# 3DAG.net
KiCad netlist of a schematic drawn in EAGLE
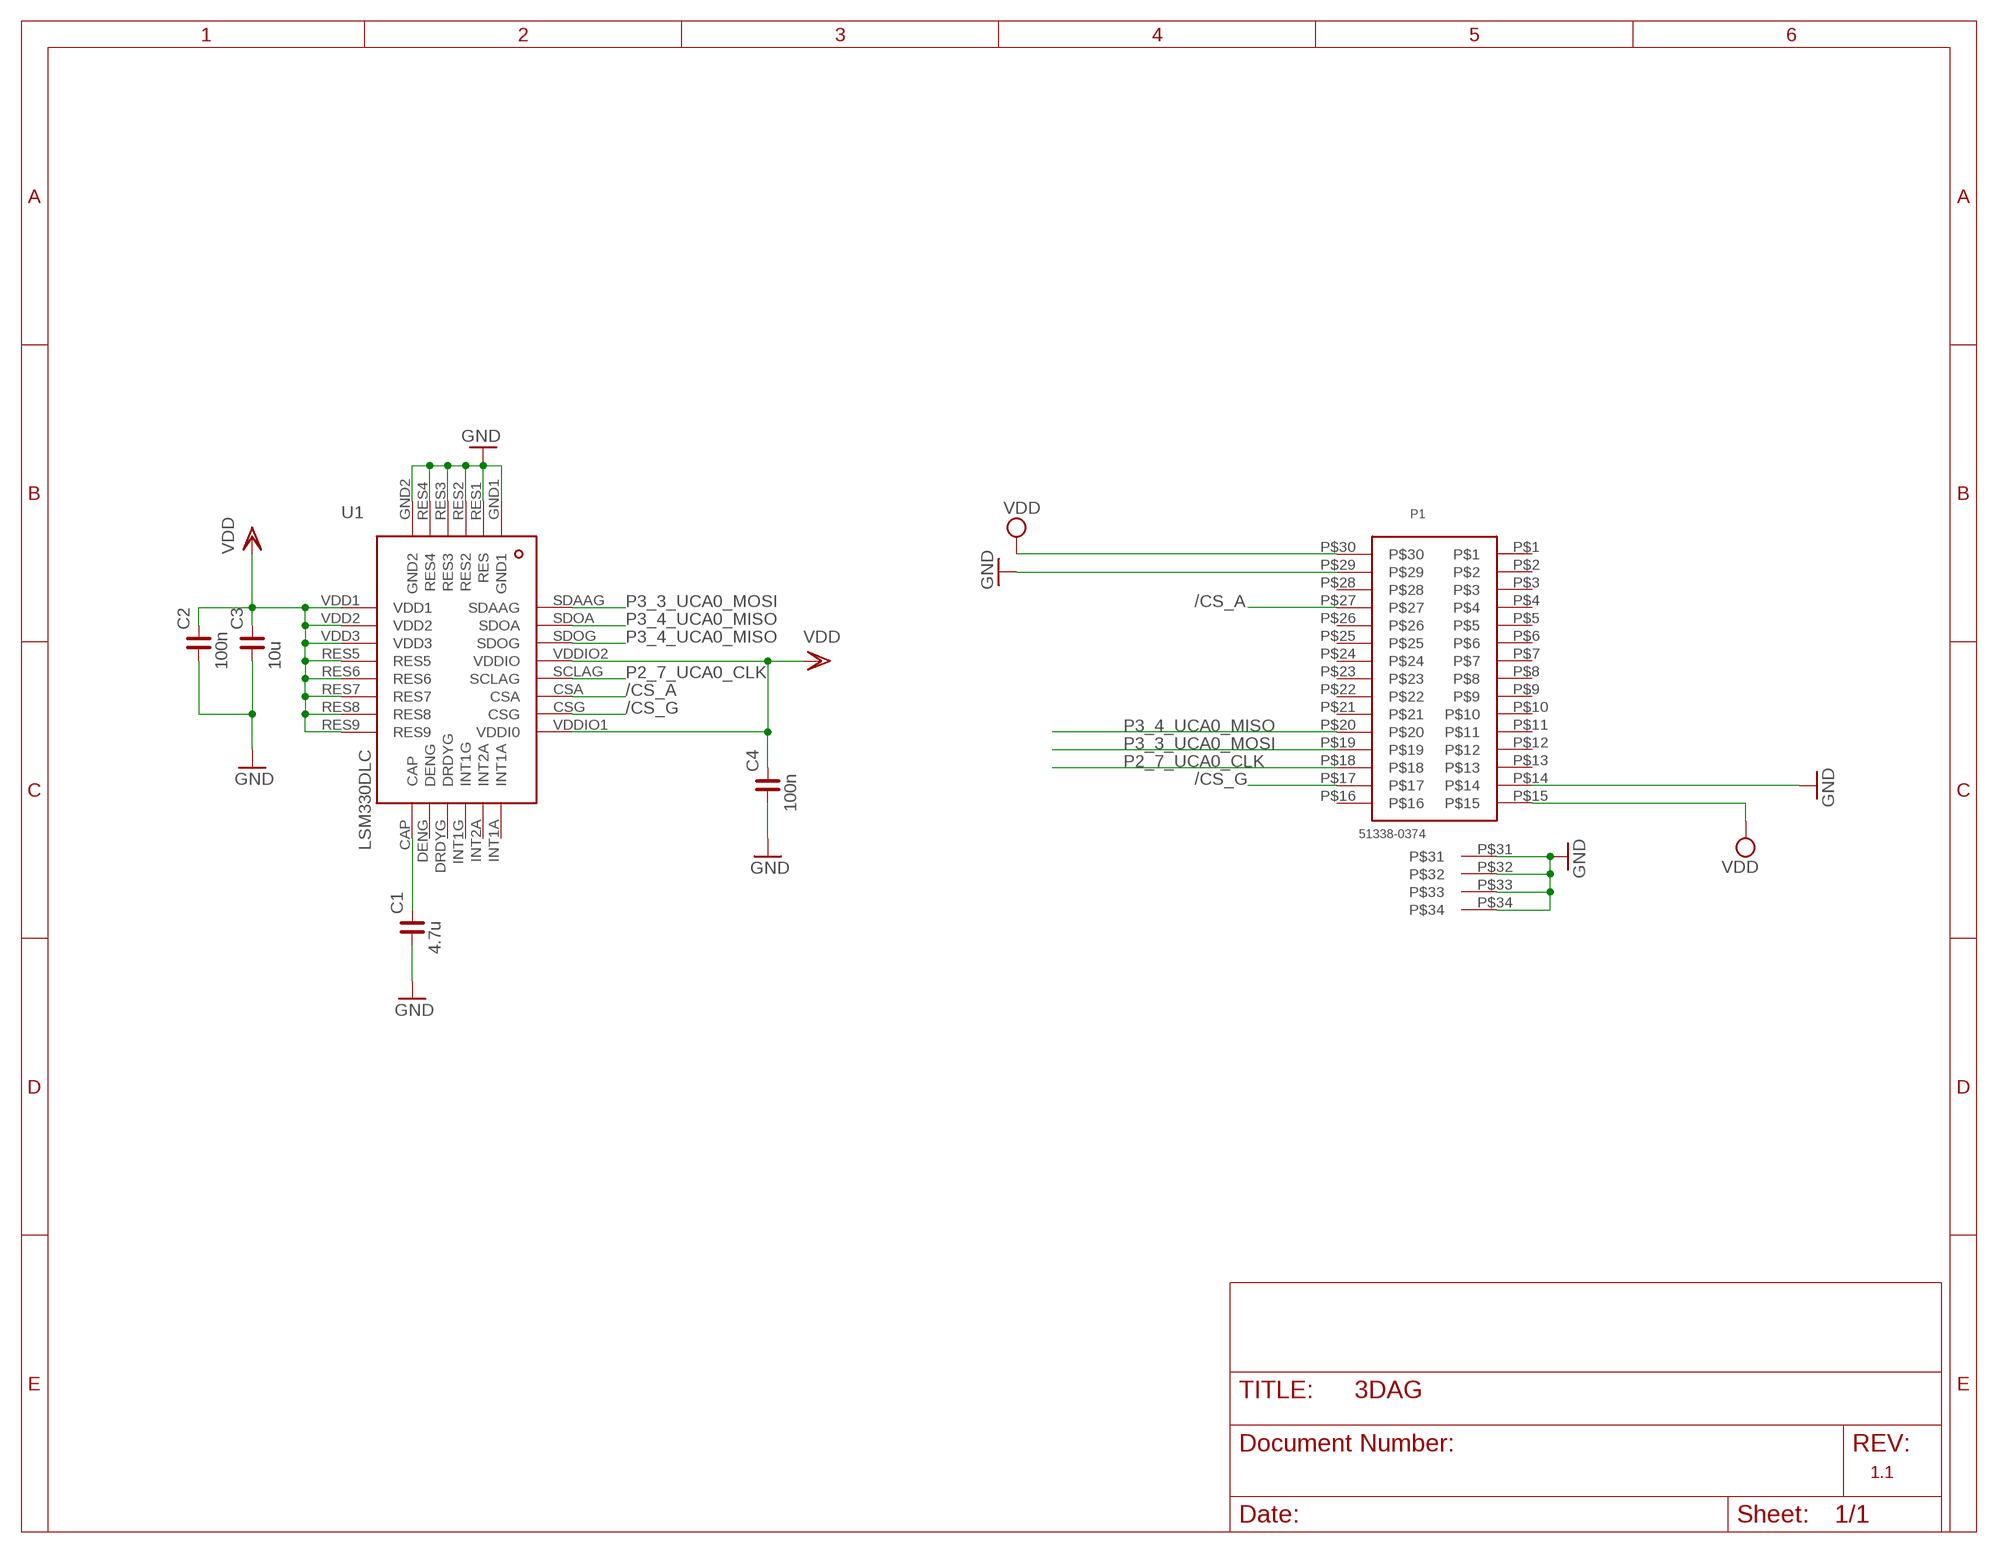
[diagram p0: schematic, sheet 1]

(export (version "E")
  (design (tool "Eeschema 10.0.6"))
  (components
    (comp (ref "C1")
      (value "4.7u")
      (footprint "eagle-import:C0402")
      (libsource (lib "eagle-import") (part "C_0402"))
    )
    (comp (ref "C2")
      (value "100n")
      (footprint "eagle-import:C0402")
      (libsource (lib "eagle-import") (part "C_0402"))
    )
    (comp (ref "C3")
      (value "10u")
      (footprint "eagle-import:C0402")
      (libsource (lib "eagle-import") (part "C_0402"))
    )
    (comp (ref "C4")
      (value "100n")
      (footprint "eagle-import:C0402")
      (libsource (lib "eagle-import") (part "C_0402"))
    )
    (comp (ref "P1")
      (value "51338-0374")
      (footprint "eagle-import:51338-0374_RECEPTACLE")
      (libsource (lib "eagle-import") (part "51338-0374_RECEPTACLE"))
    )
    (comp (ref "U$4")
      (value "LSM330DLC")
      (footprint "eagle-import:LSM330DLC")
      (libsource (lib "eagle-import") (part "LSM330DLC"))
    )
  )
  (nets
    (net (code "1") (name "/P2_7_UCA0_CLK") (class "Default")
      (node (ref "P1") (pin "P$18") (pinfunction "P$18_P$18") (pintype "bidirectional"))
      (node (ref "U$4") (pin "SCLAG") (pinfunction "SCLAG_SCLAG") (pintype "input"))
    )
    (net (code "2") (name "/P3_3_UCA0_MOSI") (class "Default")
      (node (ref "P1") (pin "P$19") (pinfunction "P$19_P$19") (pintype "bidirectional"))
      (node (ref "U$4") (pin "SDAAG") (pinfunction "SDAAG_SDAAG") (pintype "bidirectional"))
    )
    (net (code "3") (name "/P3_4_UCA0_MISO") (class "Default")
      (node (ref "P1") (pin "P$20") (pinfunction "P$20_P$20") (pintype "bidirectional"))
      (node (ref "U$4") (pin "SDOA") (pinfunction "SDOA_SDOA") (pintype "bidirectional"))
      (node (ref "U$4") (pin "SDOG") (pinfunction "SDOG_SDOG") (pintype "bidirectional"))
    )
    (net (code "4") (name "/{slash}CS_A") (class "Default")
      (node (ref "P1") (pin "P$27") (pinfunction "P$27_P$27") (pintype "bidirectional"))
      (node (ref "U$4") (pin "CSA") (pinfunction "CSA_CSA") (pintype "input"))
    )
    (net (code "5") (name "/{slash}CS_G") (class "Default")
      (node (ref "P1") (pin "P$17") (pinfunction "P$17_P$17") (pintype "bidirectional"))
      (node (ref "U$4") (pin "CSG") (pinfunction "CSG_CSG") (pintype "input"))
    )
    (net (code "6") (name "GND") (class "Default")
      (node (ref "C1") (pin "1") (pinfunction "1_1") (pintype "passive"))
      (node (ref "C2") (pin "1") (pinfunction "1_1") (pintype "passive"))
      (node (ref "C3") (pin "1") (pinfunction "1_1") (pintype "passive"))
      (node (ref "C4") (pin "1") (pinfunction "1_1") (pintype "passive"))
      (node (ref "P1") (pin "P$14") (pinfunction "P$14_P$14") (pintype "bidirectional"))
      (node (ref "P1") (pin "P$29") (pinfunction "P$29_P$29") (pintype "bidirectional"))
      (node (ref "P1") (pin "P$31") (pinfunction "P$31_P$31") (pintype "bidirectional"))
      (node (ref "P1") (pin "P$32") (pinfunction "P$32_P$32") (pintype "bidirectional"))
      (node (ref "P1") (pin "P$33") (pinfunction "P$33_P$33") (pintype "bidirectional"))
      (node (ref "P1") (pin "P$34") (pinfunction "P$34_P$34") (pintype "bidirectional"))
      (node (ref "U$4") (pin "GND1") (pinfunction "GND1_GND1") (pintype "power_in"))
      (node (ref "U$4") (pin "GND2") (pinfunction "GND2_GND2") (pintype "power_in"))
      (node (ref "U$4") (pin "RES1") (pinfunction "RES_RES1") (pintype "power_in"))
      (node (ref "U$4") (pin "RES2") (pinfunction "RES2_RES2") (pintype "power_in"))
      (node (ref "U$4") (pin "RES3") (pinfunction "RES3_RES3") (pintype "bidirectional"))
      (node (ref "U$4") (pin "RES4") (pinfunction "RES4_RES4") (pintype "bidirectional"))
    )
    (net (code "7") (name "Net-(C1-Pad2)") (class "Default")
      (node (ref "C1") (pin "2") (pinfunction "2_2") (pintype "passive"))
      (node (ref "U$4") (pin "CAP") (pinfunction "CAP_CAP") (pintype "passive"))
    )
    (net (code "8") (name "VDD") (class "Default")
      (node (ref "C2") (pin "2") (pinfunction "2_2") (pintype "passive"))
      (node (ref "C3") (pin "2") (pinfunction "2_2") (pintype "passive"))
      (node (ref "C4") (pin "2") (pinfunction "2_2") (pintype "passive"))
      (node (ref "P1") (pin "P$15") (pinfunction "P$15_P$15") (pintype "bidirectional"))
      (node (ref "P1") (pin "P$30") (pinfunction "P$30_P$30") (pintype "bidirectional"))
      (node (ref "U$4") (pin "RES5") (pinfunction "RES5_RES5") (pintype "bidirectional"))
      (node (ref "U$4") (pin "RES6") (pinfunction "RES6_RES6") (pintype "bidirectional"))
      (node (ref "U$4") (pin "RES7") (pinfunction "RES7_RES7") (pintype "bidirectional"))
      (node (ref "U$4") (pin "RES8") (pinfunction "RES8_RES8") (pintype "bidirectional"))
      (node (ref "U$4") (pin "RES9") (pinfunction "RES9_RES9") (pintype "bidirectional"))
      (node (ref "U$4") (pin "VDD1") (pinfunction "VDD1_VDD1") (pintype "power_in"))
      (node (ref "U$4") (pin "VDD2") (pinfunction "VDD2_VDD2") (pintype "power_in"))
      (node (ref "U$4") (pin "VDD3") (pinfunction "VDD3_VDD3") (pintype "power_in"))
      (node (ref "U$4") (pin "VDDIO1") (pinfunction "VDDI0_VDDIO1") (pintype "power_in"))
      (node (ref "U$4") (pin "VDDIO2") (pinfunction "VDDIO_VDDIO2") (pintype "power_in"))
    )
    (net (code "9") (name "unconnected-(P1-PadP$1)") (class "Default")
      (node (ref "P1") (pin "P$1") (pinfunction "P$1_P$1") (pintype "bidirectional"))
    )
    (net (code "10") (name "unconnected-(P1-PadP$2)") (class "Default")
      (node (ref "P1") (pin "P$2") (pinfunction "P$2_P$2") (pintype "bidirectional"))
    )
    (net (code "11") (name "unconnected-(P1-PadP$3)") (class "Default")
      (node (ref "P1") (pin "P$3") (pinfunction "P$3_P$3") (pintype "bidirectional"))
    )
    (net (code "12") (name "unconnected-(P1-PadP$4)") (class "Default")
      (node (ref "P1") (pin "P$4") (pinfunction "P$4_P$4") (pintype "bidirectional"))
    )
    (net (code "13") (name "unconnected-(P1-PadP$5)") (class "Default")
      (node (ref "P1") (pin "P$5") (pinfunction "P$5_P$5") (pintype "bidirectional"))
    )
    (net (code "14") (name "unconnected-(P1-PadP$6)") (class "Default")
      (node (ref "P1") (pin "P$6") (pinfunction "P$6_P$6") (pintype "bidirectional"))
    )
    (net (code "15") (name "unconnected-(P1-PadP$7)") (class "Default")
      (node (ref "P1") (pin "P$7") (pinfunction "P$7_P$7") (pintype "bidirectional"))
    )
    (net (code "16") (name "unconnected-(P1-PadP$8)") (class "Default")
      (node (ref "P1") (pin "P$8") (pinfunction "P$8_P$8") (pintype "bidirectional"))
    )
    (net (code "17") (name "unconnected-(P1-PadP$9)") (class "Default")
      (node (ref "P1") (pin "P$9") (pinfunction "P$9_P$9") (pintype "bidirectional"))
    )
    (net (code "18") (name "unconnected-(P1-PadP$10)") (class "Default")
      (node (ref "P1") (pin "P$10") (pinfunction "P$10_P$10") (pintype "bidirectional"))
    )
    (net (code "19") (name "unconnected-(P1-PadP$11)") (class "Default")
      (node (ref "P1") (pin "P$11") (pinfunction "P$11_P$11") (pintype "bidirectional"))
    )
    (net (code "20") (name "unconnected-(P1-PadP$12)") (class "Default")
      (node (ref "P1") (pin "P$12") (pinfunction "P$12_P$12") (pintype "bidirectional"))
    )
    (net (code "21") (name "unconnected-(P1-PadP$13)") (class "Default")
      (node (ref "P1") (pin "P$13") (pinfunction "P$13_P$13") (pintype "bidirectional"))
    )
    (net (code "22") (name "unconnected-(P1-PadP$16)") (class "Default")
      (node (ref "P1") (pin "P$16") (pinfunction "P$16_P$16") (pintype "bidirectional"))
    )
    (net (code "23") (name "unconnected-(P1-PadP$21)") (class "Default")
      (node (ref "P1") (pin "P$21") (pinfunction "P$21_P$21") (pintype "bidirectional"))
    )
    (net (code "24") (name "unconnected-(P1-PadP$22)") (class "Default")
      (node (ref "P1") (pin "P$22") (pinfunction "P$22_P$22") (pintype "bidirectional"))
    )
    (net (code "25") (name "unconnected-(P1-PadP$23)") (class "Default")
      (node (ref "P1") (pin "P$23") (pinfunction "P$23_P$23") (pintype "bidirectional"))
    )
    (net (code "26") (name "unconnected-(P1-PadP$24)") (class "Default")
      (node (ref "P1") (pin "P$24") (pinfunction "P$24_P$24") (pintype "bidirectional"))
    )
    (net (code "27") (name "unconnected-(P1-PadP$25)") (class "Default")
      (node (ref "P1") (pin "P$25") (pinfunction "P$25_P$25") (pintype "bidirectional"))
    )
    (net (code "28") (name "unconnected-(P1-PadP$26)") (class "Default")
      (node (ref "P1") (pin "P$26") (pinfunction "P$26_P$26") (pintype "bidirectional"))
    )
    (net (code "29") (name "unconnected-(P1-PadP$28)") (class "Default")
      (node (ref "P1") (pin "P$28") (pinfunction "P$28_P$28") (pintype "bidirectional"))
    )
    (net (code "30") (name "unconnected-(U$4-PadDENG)") (class "Default")
      (node (ref "U$4") (pin "DENG") (pinfunction "DENG_DENG") (pintype "input"))
    )
    (net (code "31") (name "unconnected-(U$4-PadDRDYG)") (class "Default")
      (node (ref "U$4") (pin "DRDYG") (pinfunction "DRDYG_DRDYG") (pintype "output"))
    )
    (net (code "32") (name "unconnected-(U$4-PadINT1A)") (class "Default")
      (node (ref "U$4") (pin "INT1A") (pinfunction "INT1A_INT1A") (pintype "output"))
    )
    (net (code "33") (name "unconnected-(U$4-PadINT1G)") (class "Default")
      (node (ref "U$4") (pin "INT1G") (pinfunction "INT1G_INT1G") (pintype "output"))
    )
    (net (code "34") (name "unconnected-(U$4-PadINT2A)") (class "Default")
      (node (ref "U$4") (pin "INT2A") (pinfunction "INT2A_INT2A") (pintype "output"))
    )
  )
)
